# dram1.net
KiCad netlist of a schematic drawn in Altium Designer
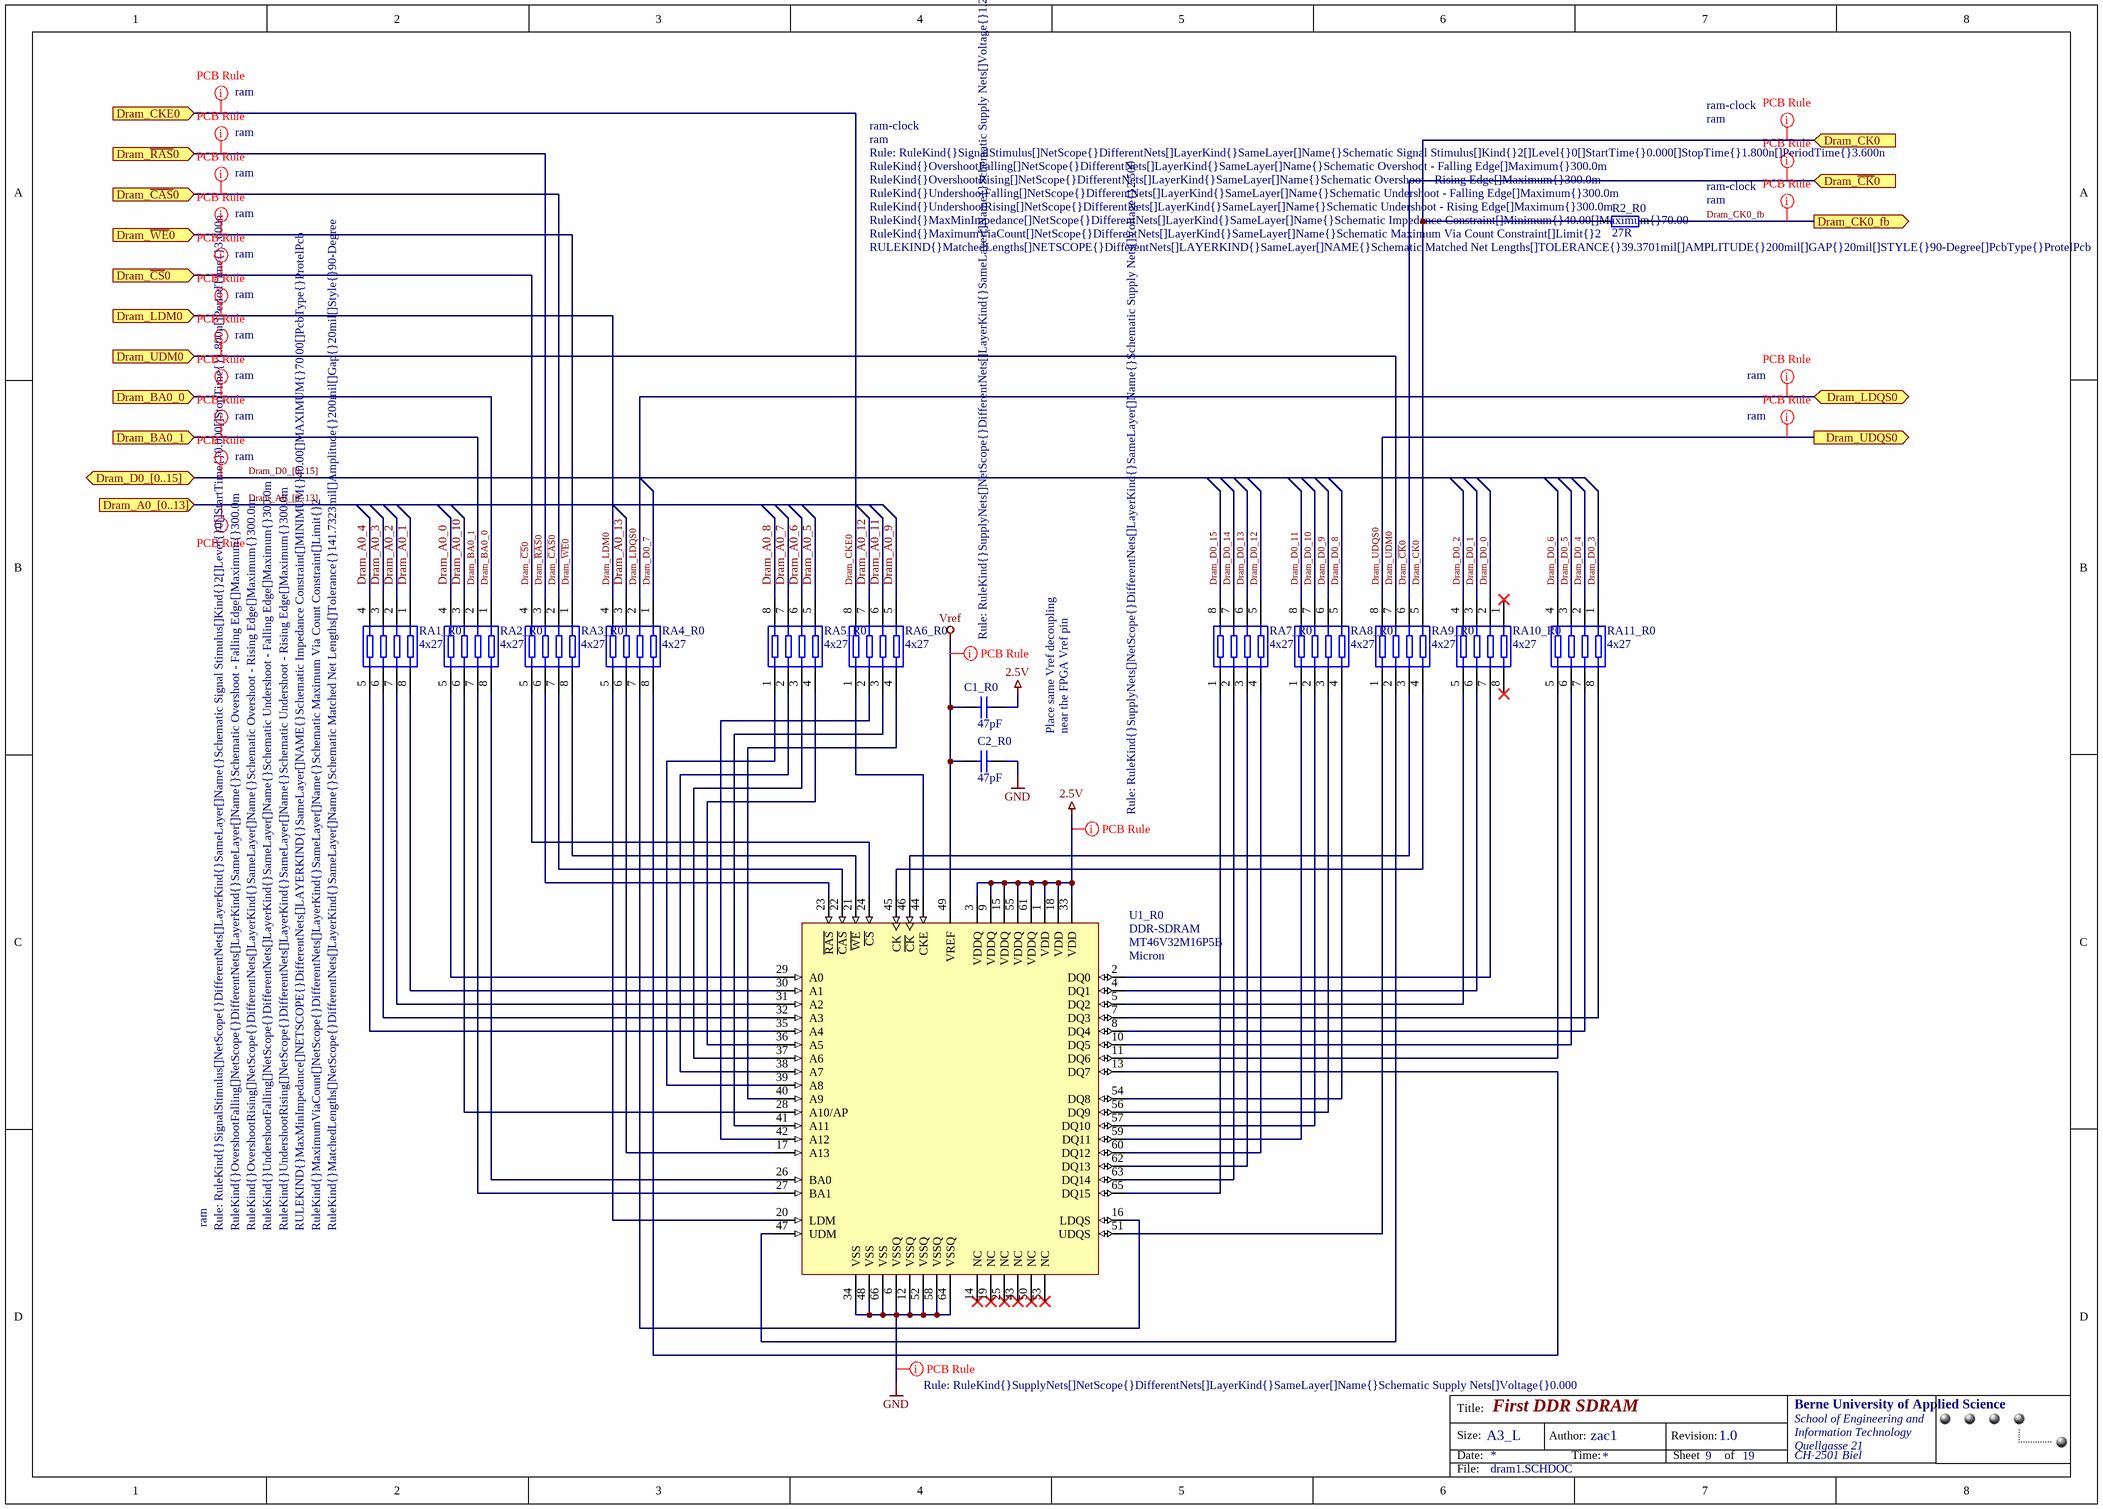
[diagram p0: dram1.SCHDOC]

(export (version "E")
  (design (tool "Eeschema 10.0.6"))
  (components
    (comp (ref "C1_R0")
      (value "47pF")
      (footprint "0402")
      (description "Capacitor")
      (fields
        (field (name "MANUFACTURER") "Murata")
        (field (name "PART NUMBER") "GRM1555C1H470JZ01D")
        (field (name "PUBLISHER") "Altium Limited")
      )
      (libsource (lib "Miscellaneous Devices") (part "Cap"))
    )
    (comp (ref "C2_R0")
      (value "47pF")
      (footprint "0402")
      (description "Capacitor")
      (fields
        (field (name "MANUFACTURER") "Murata")
        (field (name "PART NUMBER") "GRM1555C1H470JZ01D")
        (field (name "PUBLISHER") "Altium Limited")
      )
      (libsource (lib "Miscellaneous Devices") (part "Cap"))
    )
    (comp (ref "R2_R0")
      (value "27R")
      (footprint "0402")
      (description "Resistor")
      (fields
        (field (name "MANUFACTURER") "PHYCOMP")
        (field (name "PART NUMBER") "232270672709")
        (field (name "PUBLISHER") "Altium Limited")
      )
      (libsource (lib "Miscellaneous Devices") (part "Res2"))
    )
    (comp (ref "RA1_R0")
      (value "4x27")
      (footprint "1206_ARRAY")
      (fields (field (name "MANUFACTURER") "PHYCOMP") (field (name "PART NUMBER") "235003410279"))
      (libsource (lib "CoolARM-Kit") (part "R_ARRAY_4_SMD"))
    )
    (comp (ref "RA2_R0")
      (value "4x27")
      (footprint "1206_ARRAY")
      (fields (field (name "MANUFACTURER") "PHYCOMP") (field (name "PART NUMBER") "235003410279"))
      (libsource (lib "CoolARM-Kit") (part "R_ARRAY_4_SMD"))
    )
    (comp (ref "RA3_R0")
      (value "4x27")
      (footprint "1206_ARRAY")
      (fields (field (name "MANUFACTURER") "PHYCOMP") (field (name "PART NUMBER") "235003410279"))
      (libsource (lib "CoolARM-Kit") (part "R_ARRAY_4_SMD"))
    )
    (comp (ref "RA4_R0")
      (value "4x27")
      (footprint "1206_ARRAY")
      (fields (field (name "MANUFACTURER") "PHYCOMP") (field (name "PART NUMBER") "235003410279"))
      (libsource (lib "CoolARM-Kit") (part "R_ARRAY_4_SMD"))
    )
    (comp (ref "RA5_R0")
      (value "4x27")
      (footprint "1206_ARRAY")
      (fields (field (name "MANUFACTURER") "PHYCOMP") (field (name "PART NUMBER") "235003410279"))
      (libsource (lib "CoolARM-Kit") (part "R_ARRAY_4_SMD"))
    )
    (comp (ref "RA6_R0")
      (value "4x27")
      (footprint "1206_ARRAY")
      (fields (field (name "MANUFACTURER") "PHYCOMP") (field (name "PART NUMBER") "235003410279"))
      (libsource (lib "CoolARM-Kit") (part "R_ARRAY_4_SMD"))
    )
    (comp (ref "RA7_R0")
      (value "4x27")
      (footprint "1206_ARRAY")
      (fields (field (name "MANUFACTURER") "PHYCOMP") (field (name "PART NUMBER") "235003410279"))
      (libsource (lib "CoolARM-Kit") (part "R_ARRAY_4_SMD"))
    )
    (comp (ref "RA8_R0")
      (value "4x27")
      (footprint "1206_ARRAY")
      (fields (field (name "MANUFACTURER") "PHYCOMP") (field (name "PART NUMBER") "235003410279"))
      (libsource (lib "CoolARM-Kit") (part "R_ARRAY_4_SMD"))
    )
    (comp (ref "RA9_R0")
      (value "4x27")
      (footprint "1206_ARRAY")
      (fields (field (name "MANUFACTURER") "PHYCOMP") (field (name "PART NUMBER") "235003410279"))
      (libsource (lib "CoolARM-Kit") (part "R_ARRAY_4_SMD"))
    )
    (comp (ref "RA10_R0")
      (value "4x27")
      (footprint "1206_ARRAY")
      (fields (field (name "MANUFACTURER") "PHYCOMP") (field (name "PART NUMBER") "235003410279"))
      (libsource (lib "CoolARM-Kit") (part "R_ARRAY_4_SMD"))
    )
    (comp (ref "RA11_R0")
      (value "4x27")
      (footprint "1206_ARRAY")
      (fields (field (name "MANUFACTURER") "PHYCOMP") (field (name "PART NUMBER") "235003410279"))
      (libsource (lib "CoolARM-Kit") (part "R_ARRAY_4_SMD"))
    )
    (comp (ref "U1_R0")
      (value "DDR-SDRAM")
      (footprint "TSOP66")
      (description "general model for ddr sdram's")
      (fields
        (field (name "ALTIUM_VALUE") "MT46V32M16P5B")
        (field (name "VENDOR") "Micron")
        (field (name "MANUFACTURER") "Micron")
        (field (name "PART NUMBER") "MT46V32M16P5B")
      )
      (libsource (lib "gecko3-user") (part "DDR-SDRAM"))
    )
  )
  (nets
    (net (code "1") (name "/Dram_A0_0") (class "Default")
      (node (ref "RA2_R0") (pin "4") (pinfunction "4_4") (pintype "passive"))
    )
    (net (code "2") (name "/Dram_A0_1") (class "Default")
      (node (ref "RA1_R0") (pin "1") (pinfunction "1_1") (pintype "passive"))
    )
    (net (code "3") (name "/Dram_A0_2") (class "Default")
      (node (ref "RA1_R0") (pin "2") (pinfunction "2_2") (pintype "passive"))
    )
    (net (code "4") (name "/Dram_A0_3") (class "Default")
      (node (ref "RA1_R0") (pin "3") (pinfunction "3_3") (pintype "passive"))
    )
    (net (code "5") (name "/Dram_A0_4") (class "Default")
      (node (ref "RA1_R0") (pin "4") (pinfunction "4_4") (pintype "passive"))
    )
    (net (code "6") (name "/Dram_A0_5") (class "Default")
      (node (ref "RA5_R0") (pin "5") (pinfunction "5_5") (pintype "passive"))
    )
    (net (code "7") (name "/Dram_A0_6") (class "Default")
      (node (ref "RA5_R0") (pin "6") (pinfunction "6_6") (pintype "passive"))
    )
    (net (code "8") (name "/Dram_A0_7") (class "Default")
      (node (ref "RA5_R0") (pin "7") (pinfunction "7_7") (pintype "passive"))
    )
    (net (code "9") (name "/Dram_A0_8") (class "Default")
      (node (ref "RA5_R0") (pin "8") (pinfunction "8_8") (pintype "passive"))
    )
    (net (code "10") (name "/Dram_A0_9") (class "Default")
      (node (ref "RA6_R0") (pin "5") (pinfunction "5_5") (pintype "passive"))
    )
    (net (code "11") (name "/Dram_A0_10") (class "Default")
      (node (ref "RA2_R0") (pin "3") (pinfunction "3_3") (pintype "passive"))
    )
    (net (code "12") (name "/Dram_A0_11") (class "Default")
      (node (ref "RA6_R0") (pin "6") (pinfunction "6_6") (pintype "passive"))
    )
    (net (code "13") (name "/Dram_A0_12") (class "Default")
      (node (ref "RA6_R0") (pin "7") (pinfunction "7_7") (pintype "passive"))
    )
    (net (code "14") (name "/Dram_A0_13") (class "Default")
      (node (ref "RA4_R0") (pin "3") (pinfunction "3_3") (pintype "passive"))
    )
    (net (code "16") (name "/Dram_BA0_0") (class "Default")
      (node (ref "RA2_R0") (pin "1") (pinfunction "1_1") (pintype "passive"))
    )
    (net (code "17") (name "/Dram_BA0_1") (class "Default")
      (node (ref "RA2_R0") (pin "2") (pinfunction "2_2") (pintype "passive"))
    )
    (net (code "18") (name "/Dram_CK0") (class "Default")
      (node (ref "R2_R0") (pin "2") (pinfunction "2_2") (pintype "passive"))
      (node (ref "RA9_R0") (pin "5") (pinfunction "5_5") (pintype "passive"))
    )
    (net (code "19") (name "/Dram_CK0_fb") (class "Default")
      (node (ref "R2_R0") (pin "1") (pinfunction "1_1") (pintype "passive"))
    )
    (net (code "20") (name "/Dram_CKE0") (class "Default")
      (node (ref "RA6_R0") (pin "8") (pinfunction "8_8") (pintype "passive"))
    )
    (net (code "21") (name "/Dram_D0_0") (class "Default")
      (node (ref "RA10_R0") (pin "2") (pinfunction "2_2") (pintype "passive"))
    )
    (net (code "22") (name "/Dram_D0_1") (class "Default")
      (node (ref "RA10_R0") (pin "3") (pinfunction "3_3") (pintype "passive"))
    )
    (net (code "23") (name "/Dram_D0_2") (class "Default")
      (node (ref "RA10_R0") (pin "4") (pinfunction "4_4") (pintype "passive"))
    )
    (net (code "24") (name "/Dram_D0_3") (class "Default")
      (node (ref "RA11_R0") (pin "1") (pinfunction "1_1") (pintype "passive"))
    )
    (net (code "25") (name "/Dram_D0_4") (class "Default")
      (node (ref "RA11_R0") (pin "2") (pinfunction "2_2") (pintype "passive"))
    )
    (net (code "26") (name "/Dram_D0_5") (class "Default")
      (node (ref "RA11_R0") (pin "3") (pinfunction "3_3") (pintype "passive"))
    )
    (net (code "27") (name "/Dram_D0_6") (class "Default")
      (node (ref "RA11_R0") (pin "4") (pinfunction "4_4") (pintype "passive"))
    )
    (net (code "28") (name "/Dram_D0_7") (class "Default")
      (node (ref "RA4_R0") (pin "1") (pinfunction "1_1") (pintype "passive"))
    )
    (net (code "29") (name "/Dram_D0_8") (class "Default")
      (node (ref "RA8_R0") (pin "5") (pinfunction "5_5") (pintype "passive"))
    )
    (net (code "30") (name "/Dram_D0_9") (class "Default")
      (node (ref "RA8_R0") (pin "6") (pinfunction "6_6") (pintype "passive"))
    )
    (net (code "31") (name "/Dram_D0_10") (class "Default")
      (node (ref "RA8_R0") (pin "7") (pinfunction "7_7") (pintype "passive"))
    )
    (net (code "32") (name "/Dram_D0_11") (class "Default")
      (node (ref "RA8_R0") (pin "8") (pinfunction "8_8") (pintype "passive"))
    )
    (net (code "33") (name "/Dram_D0_12") (class "Default")
      (node (ref "RA7_R0") (pin "5") (pinfunction "5_5") (pintype "passive"))
    )
    (net (code "34") (name "/Dram_D0_13") (class "Default")
      (node (ref "RA7_R0") (pin "6") (pinfunction "6_6") (pintype "passive"))
    )
    (net (code "35") (name "/Dram_D0_14") (class "Default")
      (node (ref "RA7_R0") (pin "7") (pinfunction "7_7") (pintype "passive"))
    )
    (net (code "36") (name "/Dram_D0_15") (class "Default")
      (node (ref "RA7_R0") (pin "8") (pinfunction "8_8") (pintype "passive"))
    )
    (net (code "38") (name "/Dram_LDM0") (class "Default")
      (node (ref "RA4_R0") (pin "4") (pinfunction "4_4") (pintype "passive"))
    )
    (net (code "39") (name "/Dram_LDQS0") (class "Default")
      (node (ref "RA4_R0") (pin "2") (pinfunction "2_2") (pintype "passive"))
    )
    (net (code "40") (name "/Dram_UDM0") (class "Default")
      (node (ref "RA9_R0") (pin "7") (pinfunction "7_7") (pintype "passive"))
    )
    (net (code "41") (name "/Dram_UDQS0") (class "Default")
      (node (ref "RA9_R0") (pin "8") (pinfunction "8_8") (pintype "passive"))
    )
    (net (code "42") (name "/Dram_~{CAS}0") (class "Default")
      (node (ref "RA3_R0") (pin "2") (pinfunction "2_2") (pintype "passive"))
    )
    (net (code "43") (name "/Dram_~{CK}0") (class "Default")
      (node (ref "RA9_R0") (pin "6") (pinfunction "6_6") (pintype "passive"))
    )
    (net (code "44") (name "/Dram_~{CS}0") (class "Default")
      (node (ref "RA3_R0") (pin "4") (pinfunction "4_4") (pintype "passive"))
    )
    (net (code "45") (name "/Dram_~{RAS}0") (class "Default")
      (node (ref "RA3_R0") (pin "3") (pinfunction "3_3") (pintype "passive"))
    )
    (net (code "46") (name "/Dram_~{WE}0") (class "Default")
      (node (ref "RA3_R0") (pin "1") (pinfunction "1_1") (pintype "passive"))
    )
    (net (code "47") (name "2.5V") (class "Default")
      (node (ref "C1_R0") (pin "1") (pinfunction "1_1") (pintype "passive"))
      (node (ref "U1_R0") (pin "1") (pinfunction "VDD_1") (pintype "power_in"))
      (node (ref "U1_R0") (pin "15") (pinfunction "VDDQ_15") (pintype "power_in"))
      (node (ref "U1_R0") (pin "18") (pinfunction "VDD_18") (pintype "power_in"))
      (node (ref "U1_R0") (pin "3") (pinfunction "VDDQ_3") (pintype "power_in"))
      (node (ref "U1_R0") (pin "33") (pinfunction "VDD_33") (pintype "power_in"))
      (node (ref "U1_R0") (pin "55") (pinfunction "VDDQ_55") (pintype "power_in"))
      (node (ref "U1_R0") (pin "61") (pinfunction "VDDQ_61") (pintype "power_in"))
      (node (ref "U1_R0") (pin "9") (pinfunction "VDDQ_9") (pintype "power_in"))
    )
    (net (code "48") (name "GND") (class "Default")
      (node (ref "C2_R0") (pin "1") (pinfunction "1_1") (pintype "passive"))
      (node (ref "U1_R0") (pin "12") (pinfunction "VSSQ_12") (pintype "power_in"))
      (node (ref "U1_R0") (pin "34") (pinfunction "VSS_34") (pintype "power_in"))
      (node (ref "U1_R0") (pin "48") (pinfunction "VSS_48") (pintype "power_in"))
      (node (ref "U1_R0") (pin "52") (pinfunction "VSSQ_52") (pintype "power_in"))
      (node (ref "U1_R0") (pin "58") (pinfunction "VSSQ_58") (pintype "power_in"))
      (node (ref "U1_R0") (pin "6") (pinfunction "VSSQ_6") (pintype "power_in"))
      (node (ref "U1_R0") (pin "64") (pinfunction "VSSQ_64") (pintype "power_in"))
      (node (ref "U1_R0") (pin "66") (pinfunction "VSS_66") (pintype "power_in"))
    )
    (net (code "49") (name "Net-(U1_R0-A0)") (class "Default")
      (node (ref "RA2_R0") (pin "5") (pinfunction "5_5") (pintype "passive"))
      (node (ref "U1_R0") (pin "29") (pinfunction "A0_29") (pintype "input"))
    )
    (net (code "50") (name "Net-(U1_R0-A1)") (class "Default")
      (node (ref "RA1_R0") (pin "8") (pinfunction "8_8") (pintype "passive"))
      (node (ref "U1_R0") (pin "30") (pinfunction "A1_30") (pintype "input"))
    )
    (net (code "51") (name "Net-(U1_R0-A2)") (class "Default")
      (node (ref "RA1_R0") (pin "7") (pinfunction "7_7") (pintype "passive"))
      (node (ref "U1_R0") (pin "31") (pinfunction "A2_31") (pintype "input"))
    )
    (net (code "52") (name "Net-(U1_R0-A3)") (class "Default")
      (node (ref "RA1_R0") (pin "6") (pinfunction "6_6") (pintype "passive"))
      (node (ref "U1_R0") (pin "32") (pinfunction "A3_32") (pintype "input"))
    )
    (net (code "53") (name "Net-(U1_R0-A4)") (class "Default")
      (node (ref "RA1_R0") (pin "5") (pinfunction "5_5") (pintype "passive"))
      (node (ref "U1_R0") (pin "35") (pinfunction "A4_35") (pintype "input"))
    )
    (net (code "54") (name "Net-(U1_R0-A5)") (class "Default")
      (node (ref "RA5_R0") (pin "4") (pinfunction "4_4") (pintype "passive"))
      (node (ref "U1_R0") (pin "36") (pinfunction "A5_36") (pintype "input"))
    )
    (net (code "55") (name "Net-(U1_R0-A6)") (class "Default")
      (node (ref "RA5_R0") (pin "3") (pinfunction "3_3") (pintype "passive"))
      (node (ref "U1_R0") (pin "37") (pinfunction "A6_37") (pintype "input"))
    )
    (net (code "56") (name "Net-(U1_R0-A7)") (class "Default")
      (node (ref "RA5_R0") (pin "2") (pinfunction "2_2") (pintype "passive"))
      (node (ref "U1_R0") (pin "38") (pinfunction "A7_38") (pintype "input"))
    )
    (net (code "57") (name "Net-(U1_R0-A8)") (class "Default")
      (node (ref "RA5_R0") (pin "1") (pinfunction "1_1") (pintype "passive"))
      (node (ref "U1_R0") (pin "39") (pinfunction "A8_39") (pintype "input"))
    )
    (net (code "58") (name "Net-(U1_R0-A9)") (class "Default")
      (node (ref "RA6_R0") (pin "4") (pinfunction "4_4") (pintype "passive"))
      (node (ref "U1_R0") (pin "40") (pinfunction "A9_40") (pintype "input"))
    )
    (net (code "59") (name "Net-(U1_R0-A10{slash}AP)") (class "Default")
      (node (ref "RA2_R0") (pin "6") (pinfunction "6_6") (pintype "passive"))
      (node (ref "U1_R0") (pin "28") (pinfunction "A10/AP_28") (pintype "input"))
    )
    (net (code "60") (name "Net-(U1_R0-A11)") (class "Default")
      (node (ref "RA6_R0") (pin "3") (pinfunction "3_3") (pintype "passive"))
      (node (ref "U1_R0") (pin "41") (pinfunction "A11_41") (pintype "input"))
    )
    (net (code "61") (name "Net-(U1_R0-A12)") (class "Default")
      (node (ref "RA6_R0") (pin "2") (pinfunction "2_2") (pintype "passive"))
      (node (ref "U1_R0") (pin "42") (pinfunction "A12_42") (pintype "input"))
    )
    (net (code "62") (name "Net-(U1_R0-A13)") (class "Default")
      (node (ref "RA4_R0") (pin "6") (pinfunction "6_6") (pintype "passive"))
      (node (ref "U1_R0") (pin "17") (pinfunction "A13_17") (pintype "input"))
    )
    (net (code "63") (name "Net-(U1_R0-BA0)") (class "Default")
      (node (ref "RA2_R0") (pin "8") (pinfunction "8_8") (pintype "passive"))
      (node (ref "U1_R0") (pin "26") (pinfunction "BA0_26") (pintype "input"))
    )
    (net (code "64") (name "Net-(U1_R0-BA1)") (class "Default")
      (node (ref "RA2_R0") (pin "7") (pinfunction "7_7") (pintype "passive"))
      (node (ref "U1_R0") (pin "27") (pinfunction "BA1_27") (pintype "input"))
    )
    (net (code "65") (name "Net-(U1_R0-CK)") (class "Default")
      (node (ref "RA9_R0") (pin "4") (pinfunction "4_4") (pintype "passive"))
      (node (ref "U1_R0") (pin "45") (pinfunction "CK_45") (pintype "input"))
    )
    (net (code "66") (name "Net-(U1_R0-CKE)") (class "Default")
      (node (ref "RA6_R0") (pin "1") (pinfunction "1_1") (pintype "passive"))
      (node (ref "U1_R0") (pin "44") (pinfunction "CKE_44") (pintype "input"))
    )
    (net (code "67") (name "Net-(U1_R0-DQ0)") (class "Default")
      (node (ref "RA10_R0") (pin "7") (pinfunction "7_7") (pintype "passive"))
      (node (ref "U1_R0") (pin "2") (pinfunction "DQ0_2") (pintype "bidirectional"))
    )
    (net (code "68") (name "Net-(U1_R0-DQ1)") (class "Default")
      (node (ref "RA10_R0") (pin "6") (pinfunction "6_6") (pintype "passive"))
      (node (ref "U1_R0") (pin "4") (pinfunction "DQ1_4") (pintype "bidirectional"))
    )
    (net (code "69") (name "Net-(U1_R0-DQ2)") (class "Default")
      (node (ref "RA10_R0") (pin "5") (pinfunction "5_5") (pintype "passive"))
      (node (ref "U1_R0") (pin "5") (pinfunction "DQ2_5") (pintype "bidirectional"))
    )
    (net (code "70") (name "Net-(U1_R0-DQ3)") (class "Default")
      (node (ref "RA11_R0") (pin "8") (pinfunction "8_8") (pintype "passive"))
      (node (ref "U1_R0") (pin "7") (pinfunction "DQ3_7") (pintype "bidirectional"))
    )
    (net (code "71") (name "Net-(U1_R0-DQ4)") (class "Default")
      (node (ref "RA11_R0") (pin "7") (pinfunction "7_7") (pintype "passive"))
      (node (ref "U1_R0") (pin "8") (pinfunction "DQ4_8") (pintype "bidirectional"))
    )
    (net (code "72") (name "Net-(U1_R0-DQ5)") (class "Default")
      (node (ref "RA11_R0") (pin "6") (pinfunction "6_6") (pintype "passive"))
      (node (ref "U1_R0") (pin "10") (pinfunction "DQ5_10") (pintype "bidirectional"))
    )
    (net (code "73") (name "Net-(U1_R0-DQ6)") (class "Default")
      (node (ref "RA11_R0") (pin "5") (pinfunction "5_5") (pintype "passive"))
      (node (ref "U1_R0") (pin "11") (pinfunction "DQ6_11") (pintype "bidirectional"))
    )
    (net (code "74") (name "Net-(U1_R0-DQ7)") (class "Default")
      (node (ref "RA4_R0") (pin "8") (pinfunction "8_8") (pintype "passive"))
      (node (ref "U1_R0") (pin "13") (pinfunction "DQ7_13") (pintype "bidirectional"))
    )
    (net (code "75") (name "Net-(U1_R0-DQ8)") (class "Default")
      (node (ref "RA8_R0") (pin "4") (pinfunction "4_4") (pintype "passive"))
      (node (ref "U1_R0") (pin "54") (pinfunction "DQ8_54") (pintype "bidirectional"))
    )
    (net (code "76") (name "Net-(U1_R0-DQ9)") (class "Default")
      (node (ref "RA8_R0") (pin "3") (pinfunction "3_3") (pintype "passive"))
      (node (ref "U1_R0") (pin "56") (pinfunction "DQ9_56") (pintype "bidirectional"))
    )
    (net (code "77") (name "Net-(U1_R0-DQ10)") (class "Default")
      (node (ref "RA8_R0") (pin "2") (pinfunction "2_2") (pintype "passive"))
      (node (ref "U1_R0") (pin "57") (pinfunction "DQ10_57") (pintype "bidirectional"))
    )
    (net (code "78") (name "Net-(U1_R0-DQ11)") (class "Default")
      (node (ref "RA8_R0") (pin "1") (pinfunction "1_1") (pintype "passive"))
      (node (ref "U1_R0") (pin "59") (pinfunction "DQ11_59") (pintype "bidirectional"))
    )
    (net (code "79") (name "Net-(U1_R0-DQ12)") (class "Default")
      (node (ref "RA7_R0") (pin "4") (pinfunction "4_4") (pintype "passive"))
      (node (ref "U1_R0") (pin "60") (pinfunction "DQ12_60") (pintype "bidirectional"))
    )
    (net (code "80") (name "Net-(U1_R0-DQ13)") (class "Default")
      (node (ref "RA7_R0") (pin "3") (pinfunction "3_3") (pintype "passive"))
      (node (ref "U1_R0") (pin "62") (pinfunction "DQ13_62") (pintype "bidirectional"))
    )
    (net (code "81") (name "Net-(U1_R0-DQ14)") (class "Default")
      (node (ref "RA7_R0") (pin "2") (pinfunction "2_2") (pintype "passive"))
      (node (ref "U1_R0") (pin "63") (pinfunction "DQ14_63") (pintype "bidirectional"))
    )
    (net (code "82") (name "Net-(U1_R0-DQ15)") (class "Default")
      (node (ref "RA7_R0") (pin "1") (pinfunction "1_1") (pintype "passive"))
      (node (ref "U1_R0") (pin "65") (pinfunction "DQ15_65") (pintype "bidirectional"))
    )
    (net (code "83") (name "Net-(U1_R0-LDM)") (class "Default")
      (node (ref "RA4_R0") (pin "5") (pinfunction "5_5") (pintype "passive"))
      (node (ref "U1_R0") (pin "20") (pinfunction "LDM_20") (pintype "input"))
    )
    (net (code "84") (name "Net-(U1_R0-LDQS)") (class "Default")
      (node (ref "RA4_R0") (pin "7") (pinfunction "7_7") (pintype "passive"))
      (node (ref "U1_R0") (pin "16") (pinfunction "LDQS_16") (pintype "bidirectional"))
    )
    (net (code "85") (name "Net-(U1_R0-UDM)") (class "Default")
      (node (ref "RA9_R0") (pin "2") (pinfunction "2_2") (pintype "passive"))
      (node (ref "U1_R0") (pin "47") (pinfunction "UDM_47") (pintype "input"))
    )
    (net (code "86") (name "Net-(U1_R0-UDQS)") (class "Default")
      (node (ref "RA9_R0") (pin "1") (pinfunction "1_1") (pintype "passive"))
      (node (ref "U1_R0") (pin "51") (pinfunction "UDQS_51") (pintype "bidirectional"))
    )
    (net (code "87") (name "Net-(U1_R0-~{CAS})") (class "Default")
      (node (ref "RA3_R0") (pin "7") (pinfunction "7_7") (pintype "passive"))
      (node (ref "U1_R0") (pin "22") (pinfunction "~{CAS}_22") (pintype "input"))
    )
    (net (code "88") (name "Net-(U1_R0-~{CK})") (class "Default")
      (node (ref "RA9_R0") (pin "3") (pinfunction "3_3") (pintype "passive"))
      (node (ref "U1_R0") (pin "46") (pinfunction "~{CK}_46") (pintype "input"))
    )
    (net (code "89") (name "Net-(U1_R0-~{CS})") (class "Default")
      (node (ref "RA3_R0") (pin "5") (pinfunction "5_5") (pintype "passive"))
      (node (ref "U1_R0") (pin "24") (pinfunction "~{CS}_24") (pintype "input"))
    )
    (net (code "90") (name "Net-(U1_R0-~{RAS})") (class "Default")
      (node (ref "RA3_R0") (pin "6") (pinfunction "6_6") (pintype "passive"))
      (node (ref "U1_R0") (pin "23") (pinfunction "~{RAS}_23") (pintype "input"))
    )
    (net (code "91") (name "Net-(U1_R0-~{WE})") (class "Default")
      (node (ref "RA3_R0") (pin "8") (pinfunction "8_8") (pintype "passive"))
      (node (ref "U1_R0") (pin "21") (pinfunction "~{WE}_21") (pintype "input"))
    )
    (net (code "92") (name "Vref") (class "Default")
      (node (ref "C1_R0") (pin "2") (pinfunction "2_2") (pintype "passive"))
      (node (ref "C2_R0") (pin "2") (pinfunction "2_2") (pintype "passive"))
      (node (ref "U1_R0") (pin "49") (pinfunction "VREF_49") (pintype "power_in"))
    )
    (net (code "93") (name "unconnected-(RA10_R0-Pad1)") (class "Default")
      (node (ref "RA10_R0") (pin "1") (pinfunction "1_1") (pintype "passive+no_connect"))
    )
    (net (code "94") (name "unconnected-(RA10_R0-Pad8)") (class "Default")
      (node (ref "RA10_R0") (pin "8") (pinfunction "8_8") (pintype "passive+no_connect"))
    )
    (net (code "95") (name "unconnected-(U1_R0-NC-Pad14)") (class "Default")
      (node (ref "U1_R0") (pin "14") (pinfunction "NC_14") (pintype "passive+no_connect"))
    )
    (net (code "96") (name "unconnected-(U1_R0-NC-Pad19)") (class "Default")
      (node (ref "U1_R0") (pin "19") (pinfunction "NC_19") (pintype "passive+no_connect"))
    )
    (net (code "97") (name "unconnected-(U1_R0-NC-Pad25)") (class "Default")
      (node (ref "U1_R0") (pin "25") (pinfunction "NC_25") (pintype "passive+no_connect"))
    )
    (net (code "98") (name "unconnected-(U1_R0-NC-Pad43)") (class "Default")
      (node (ref "U1_R0") (pin "43") (pinfunction "NC_43") (pintype "passive+no_connect"))
    )
    (net (code "99") (name "unconnected-(U1_R0-NC-Pad50)") (class "Default")
      (node (ref "U1_R0") (pin "50") (pinfunction "NC_50") (pintype "passive+no_connect"))
    )
    (net (code "100") (name "unconnected-(U1_R0-NC-Pad53)") (class "Default")
      (node (ref "U1_R0") (pin "53") (pinfunction "NC_53") (pintype "passive+no_connect"))
    )
  )
)
